# FPGA_part2.net
KiCad netlist of a schematic drawn in Altium Designer
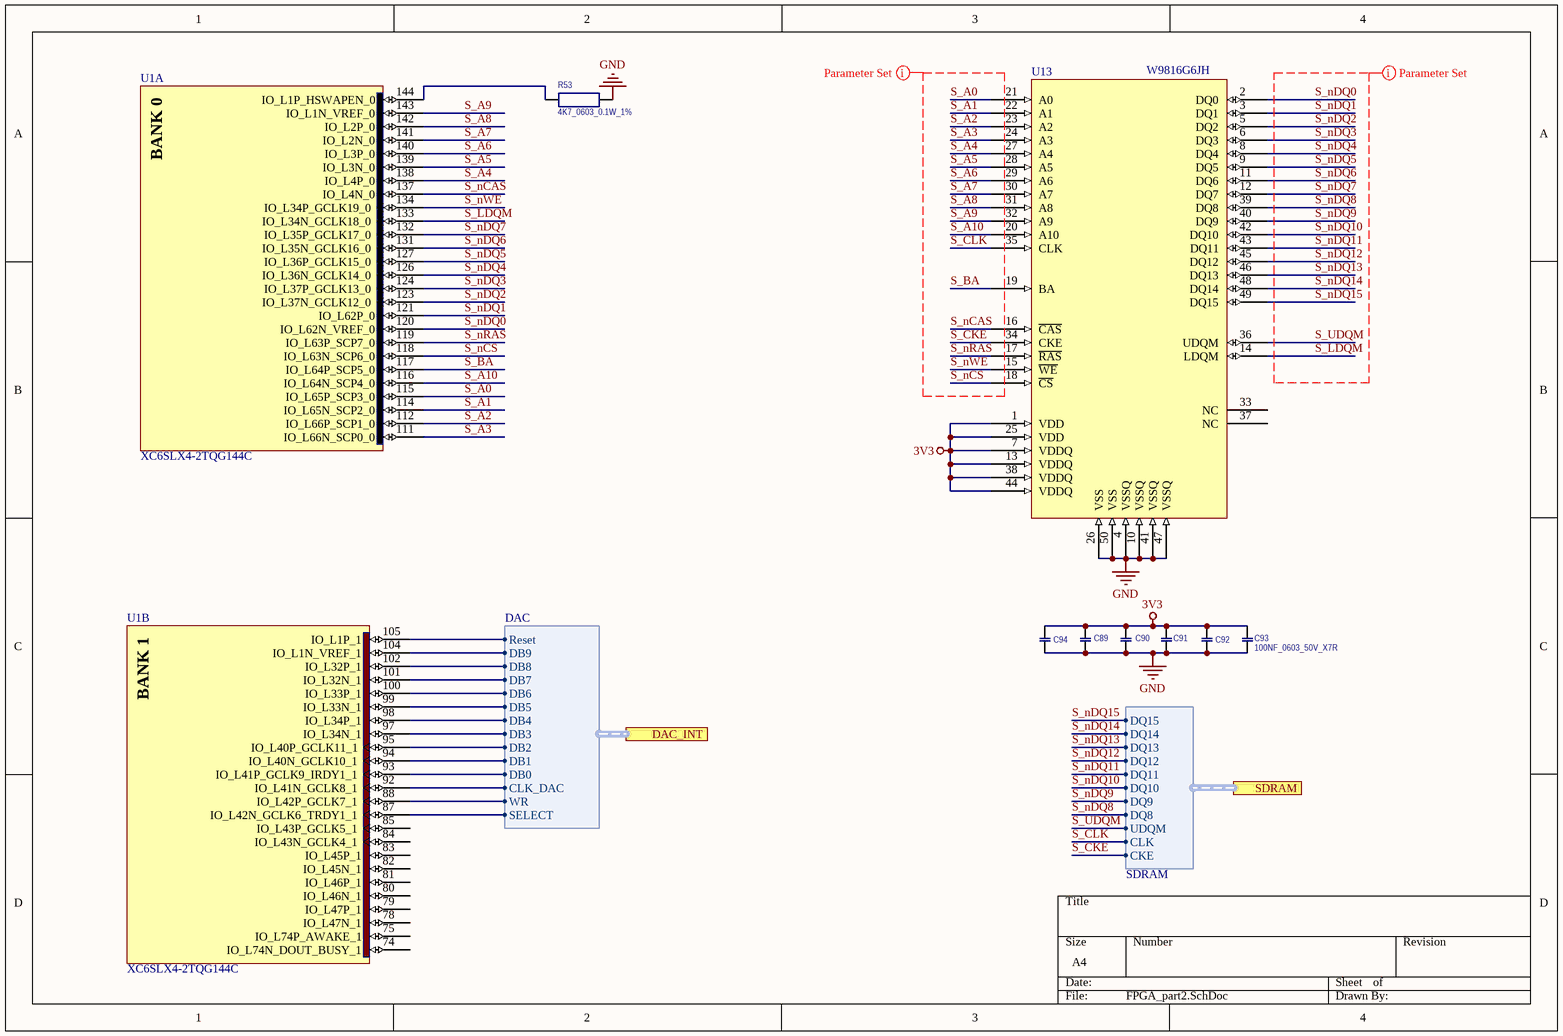
[diagram p0: FPGA_part2.SchDoc]

(export (version "E")
  (design (tool "Eeschema 10.0.6"))
  (components
    (comp (ref "C89")
      (value "100NF_0603_50V_X7R")
      (footprint "CAP0603")
      (description "128-8255    Capacitor MLC-X7R_0603_100NF_10%_50V; C0603C104K5RAC; KEMET; RoHS=Yes")
      (libsource (lib "ONEMULA_V2") (part "100NF_0603_50V_X7R"))
    )
    (comp (ref "C90")
      (value "100NF_0603_50V_X7R")
      (footprint "CAP0603")
      (description "128-8255    Capacitor MLC-X7R_0603_100NF_10%_50V; C0603C104K5RAC; KEMET; RoHS=Yes")
      (libsource (lib "ONEMULA_V2") (part "100NF_0603_50V_X7R"))
    )
    (comp (ref "C91")
      (value "100NF_0603_50V_X7R")
      (footprint "CAP0603")
      (description "128-8255    Capacitor MLC-X7R_0603_100NF_10%_50V; C0603C104K5RAC; KEMET; RoHS=Yes")
      (libsource (lib "ONEMULA_V2") (part "100NF_0603_50V_X7R"))
    )
    (comp (ref "C92")
      (value "100NF_0603_50V_X7R")
      (footprint "CAP0603")
      (description "128-8255    Capacitor MLC-X7R_0603_100NF_10%_50V; C0603C104K5RAC; KEMET; RoHS=Yes")
      (libsource (lib "ONEMULA_V2") (part "100NF_0603_50V_X7R"))
    )
    (comp (ref "C93")
      (value "100NF_0603_50V_X7R")
      (footprint "CAP0603")
      (description "128-8255    Capacitor MLC-X7R_0603_100NF_10%_50V; C0603C104K5RAC; KEMET; RoHS=Yes")
      (libsource (lib "ONEMULA_V2") (part "100NF_0603_50V_X7R"))
    )
    (comp (ref "C94")
      (value "100NF_0603_50V_X7R")
      (footprint "CAP0603")
      (description "128-8255    Capacitor MLC-X7R_0603_100NF_10%_50V; C0603C104K5RAC; KEMET; RoHS=Yes")
      (libsource (lib "ONEMULA_V2") (part "100NF_0603_50V_X7R"))
    )
    (comp (ref "R53")
      (value "4K7_0603_0.1W_1%")
      (footprint "R0603")
      (description "146-9807    RESISTOR MF_0603_4K7_0.1W_1%_75V; CRCW06034K70FKEA; VISHAY; RoHS=Yes")
      (libsource (lib "ONEMULA_V2") (part "4K7_0603_0.1W_1%"))
    )
    (comp (ref "U1")
      (value "XC6SLX4-2TQG144C")
      (footprint "TQG144_L")
      (fields (field (name "PUBLISHER") "Altium Limited"))
      (libsource (lib "Xilinx Spartan-6") (part "XC6SLX4-2TQG144C"))
    )
    (comp (ref "U13")
      (value "W9816G6JH")
      (footprint "SSOP50")
      (libsource (lib "My_library") (part "W9816G6JH"))
    )
  )
  (nets
    (net (code "3") (name "/CLK_DAC") (class "Default")
      (node (ref "U1") (pin "92") (pinfunction "IO_L41N_GCLK8_1_92") (pintype "bidirectional"))
    )
    (net (code "4") (name "/DB0") (class "Default")
      (node (ref "U1") (pin "93") (pinfunction "IO_L41P_GCLK9_IRDY1_1_93") (pintype "bidirectional"))
    )
    (net (code "5") (name "/DB1") (class "Default")
      (node (ref "U1") (pin "94") (pinfunction "IO_L40N_GCLK10_1_94") (pintype "bidirectional"))
    )
    (net (code "6") (name "/DB2") (class "Default")
      (node (ref "U1") (pin "95") (pinfunction "IO_L40P_GCLK11_1_95") (pintype "bidirectional"))
    )
    (net (code "7") (name "/DB3") (class "Default")
      (node (ref "U1") (pin "97") (pinfunction "IO_L34N_1_97") (pintype "bidirectional"))
    )
    (net (code "8") (name "/DB4") (class "Default")
      (node (ref "U1") (pin "98") (pinfunction "IO_L34P_1_98") (pintype "bidirectional"))
    )
    (net (code "9") (name "/DB5") (class "Default")
      (node (ref "U1") (pin "99") (pinfunction "IO_L33N_1_99") (pintype "bidirectional"))
    )
    (net (code "10") (name "/DB6") (class "Default")
      (node (ref "U1") (pin "100") (pinfunction "IO_L33P_1_100") (pintype "bidirectional"))
    )
    (net (code "11") (name "/DB7") (class "Default")
      (node (ref "U1") (pin "101") (pinfunction "IO_L32N_1_101") (pintype "bidirectional"))
    )
    (net (code "12") (name "/DB8") (class "Default")
      (node (ref "U1") (pin "102") (pinfunction "IO_L32P_1_102") (pintype "bidirectional"))
    )
    (net (code "13") (name "/DB9") (class "Default")
      (node (ref "U1") (pin "104") (pinfunction "IO_L1N_VREF_1_104") (pintype "bidirectional"))
    )
    (net (code "14") (name "/Reset") (class "Default")
      (node (ref "U1") (pin "105") (pinfunction "IO_L1P_1_105") (pintype "bidirectional"))
    )
    (net (code "15") (name "/SELECT") (class "Default")
      (node (ref "U1") (pin "87") (pinfunction "IO_L42N_GCLK6_TRDY1_1_87") (pintype "bidirectional"))
    )
    (net (code "16") (name "/S_A0") (class "Default")
      (node (ref "U1") (pin "115") (pinfunction "IO_L65P_SCP3_0_115") (pintype "bidirectional"))
      (node (ref "U13") (pin "21") (pinfunction "A0_21") (pintype "input"))
    )
    (net (code "17") (name "/S_A1") (class "Default")
      (node (ref "U1") (pin "114") (pinfunction "IO_L65N_SCP2_0_114") (pintype "bidirectional"))
      (node (ref "U13") (pin "22") (pinfunction "A1_22") (pintype "input"))
    )
    (net (code "18") (name "/S_A2") (class "Default")
      (node (ref "U1") (pin "112") (pinfunction "IO_L66P_SCP1_0_112") (pintype "bidirectional"))
      (node (ref "U13") (pin "23") (pinfunction "A2_23") (pintype "input"))
    )
    (net (code "19") (name "/S_A3") (class "Default")
      (node (ref "U1") (pin "111") (pinfunction "IO_L66N_SCP0_0_111") (pintype "bidirectional"))
      (node (ref "U13") (pin "24") (pinfunction "A3_24") (pintype "input"))
    )
    (net (code "20") (name "/S_A4") (class "Default")
      (node (ref "U1") (pin "138") (pinfunction "IO_L4P_0_138") (pintype "bidirectional"))
      (node (ref "U13") (pin "27") (pinfunction "A4_27") (pintype "input"))
    )
    (net (code "21") (name "/S_A5") (class "Default")
      (node (ref "U1") (pin "139") (pinfunction "IO_L3N_0_139") (pintype "bidirectional"))
      (node (ref "U13") (pin "28") (pinfunction "A5_28") (pintype "input"))
    )
    (net (code "22") (name "/S_A6") (class "Default")
      (node (ref "U1") (pin "140") (pinfunction "IO_L3P_0_140") (pintype "bidirectional"))
      (node (ref "U13") (pin "29") (pinfunction "A6_29") (pintype "input"))
    )
    (net (code "23") (name "/S_A7") (class "Default")
      (node (ref "U1") (pin "141") (pinfunction "IO_L2N_0_141") (pintype "bidirectional"))
      (node (ref "U13") (pin "30") (pinfunction "A7_30") (pintype "input"))
    )
    (net (code "24") (name "/S_A8") (class "Default")
      (node (ref "U1") (pin "142") (pinfunction "IO_L2P_0_142") (pintype "bidirectional"))
      (node (ref "U13") (pin "31") (pinfunction "A8_31") (pintype "input"))
    )
    (net (code "25") (name "/S_A9") (class "Default")
      (node (ref "U1") (pin "143") (pinfunction "IO_L1N_VREF_0_143") (pintype "bidirectional"))
      (node (ref "U13") (pin "32") (pinfunction "A9_32") (pintype "input"))
    )
    (net (code "26") (name "/S_A10") (class "Default")
      (node (ref "U1") (pin "116") (pinfunction "IO_L64N_SCP4_0_116") (pintype "bidirectional"))
      (node (ref "U13") (pin "20") (pinfunction "A10_20") (pintype "input"))
    )
    (net (code "27") (name "/S_BA") (class "Default")
      (node (ref "U1") (pin "117") (pinfunction "IO_L64P_SCP5_0_117") (pintype "bidirectional"))
      (node (ref "U13") (pin "19") (pinfunction "BA_19") (pintype "input"))
    )
    (net (code "28") (name "/S_CKE") (class "Default")
      (node (ref "U13") (pin "34") (pinfunction "CKE_34") (pintype "input"))
    )
    (net (code "29") (name "/S_CLK") (class "Default")
      (node (ref "U13") (pin "35") (pinfunction "CLK_35") (pintype "input"))
    )
    (net (code "30") (name "/S_LDQM") (class "Default")
      (node (ref "U1") (pin "133") (pinfunction "IO_L34N_GCLK18_0_133") (pintype "bidirectional"))
      (node (ref "U13") (pin "14") (pinfunction "LDQM_14") (pintype "bidirectional"))
    )
    (net (code "31") (name "/S_UDQM") (class "Default")
      (node (ref "U13") (pin "36") (pinfunction "UDQM_36") (pintype "bidirectional"))
    )
    (net (code "32") (name "/S_nCAS") (class "Default")
      (node (ref "U1") (pin "137") (pinfunction "IO_L4N_0_137") (pintype "bidirectional"))
      (node (ref "U13") (pin "16") (pinfunction "~{CAS}_16") (pintype "input"))
    )
    (net (code "33") (name "/S_nCS") (class "Default")
      (node (ref "U1") (pin "118") (pinfunction "IO_L63N_SCP6_0_118") (pintype "bidirectional"))
      (node (ref "U13") (pin "18") (pinfunction "~{CS}_18") (pintype "input"))
    )
    (net (code "34") (name "/S_nDQ0") (class "Default")
      (node (ref "U1") (pin "120") (pinfunction "IO_L62N_VREF_0_120") (pintype "bidirectional"))
      (node (ref "U13") (pin "2") (pinfunction "DQ0_2") (pintype "bidirectional"))
    )
    (net (code "35") (name "/S_nDQ1") (class "Default")
      (node (ref "U1") (pin "121") (pinfunction "IO_L62P_0_121") (pintype "bidirectional"))
      (node (ref "U13") (pin "3") (pinfunction "DQ1_3") (pintype "bidirectional"))
    )
    (net (code "36") (name "/S_nDQ2") (class "Default")
      (node (ref "U1") (pin "123") (pinfunction "IO_L37N_GCLK12_0_123") (pintype "bidirectional"))
      (node (ref "U13") (pin "5") (pinfunction "DQ2_5") (pintype "bidirectional"))
    )
    (net (code "37") (name "/S_nDQ3") (class "Default")
      (node (ref "U1") (pin "124") (pinfunction "IO_L37P_GCLK13_0_124") (pintype "bidirectional"))
      (node (ref "U13") (pin "6") (pinfunction "DQ3_6") (pintype "bidirectional"))
    )
    (net (code "38") (name "/S_nDQ4") (class "Default")
      (node (ref "U1") (pin "126") (pinfunction "IO_L36N_GCLK14_0_126") (pintype "bidirectional"))
      (node (ref "U13") (pin "8") (pinfunction "DQ4_8") (pintype "bidirectional"))
    )
    (net (code "39") (name "/S_nDQ5") (class "Default")
      (node (ref "U1") (pin "127") (pinfunction "IO_L36P_GCLK15_0_127") (pintype "bidirectional"))
      (node (ref "U13") (pin "9") (pinfunction "DQ5_9") (pintype "bidirectional"))
    )
    (net (code "40") (name "/S_nDQ6") (class "Default")
      (node (ref "U1") (pin "131") (pinfunction "IO_L35N_GCLK16_0_131") (pintype "bidirectional"))
      (node (ref "U13") (pin "11") (pinfunction "DQ6_11") (pintype "bidirectional"))
    )
    (net (code "41") (name "/S_nDQ7") (class "Default")
      (node (ref "U1") (pin "132") (pinfunction "IO_L35P_GCLK17_0_132") (pintype "bidirectional"))
      (node (ref "U13") (pin "12") (pinfunction "DQ7_12") (pintype "bidirectional"))
    )
    (net (code "42") (name "/S_nDQ8") (class "Default")
      (node (ref "U13") (pin "39") (pinfunction "DQ8_39") (pintype "bidirectional"))
    )
    (net (code "43") (name "/S_nDQ9") (class "Default")
      (node (ref "U13") (pin "40") (pinfunction "DQ9_40") (pintype "bidirectional"))
    )
    (net (code "44") (name "/S_nDQ10") (class "Default")
      (node (ref "U13") (pin "42") (pinfunction "DQ10_42") (pintype "bidirectional"))
    )
    (net (code "45") (name "/S_nDQ11") (class "Default")
      (node (ref "U13") (pin "43") (pinfunction "DQ11_43") (pintype "bidirectional"))
    )
    (net (code "46") (name "/S_nDQ12") (class "Default")
      (node (ref "U13") (pin "45") (pinfunction "DQ12_45") (pintype "bidirectional"))
    )
    (net (code "47") (name "/S_nDQ13") (class "Default")
      (node (ref "U13") (pin "46") (pinfunction "DQ13_46") (pintype "bidirectional"))
    )
    (net (code "48") (name "/S_nDQ14") (class "Default")
      (node (ref "U13") (pin "48") (pinfunction "DQ14_48") (pintype "bidirectional"))
    )
    (net (code "49") (name "/S_nDQ15") (class "Default")
      (node (ref "U13") (pin "49") (pinfunction "DQ15_49") (pintype "bidirectional"))
    )
    (net (code "50") (name "/S_nRAS") (class "Default")
      (node (ref "U1") (pin "119") (pinfunction "IO_L63P_SCP7_0_119") (pintype "bidirectional"))
      (node (ref "U13") (pin "17") (pinfunction "~{RAS}_17") (pintype "input"))
    )
    (net (code "51") (name "/S_nWE") (class "Default")
      (node (ref "U1") (pin "134") (pinfunction "IO_L34P_GCLK19_0_134") (pintype "bidirectional"))
      (node (ref "U13") (pin "15") (pinfunction "~{WE}_15") (pintype "input"))
    )
    (net (code "52") (name "/WR") (class "Default")
      (node (ref "U1") (pin "88") (pinfunction "IO_L42P_GCLK7_1_88") (pintype "bidirectional"))
    )
    (net (code "55") (name "3V3") (class "Default")
      (node (ref "C89") (pin "1") (pinfunction "1_1") (pintype "passive"))
      (node (ref "C90") (pin "1") (pinfunction "1_1") (pintype "passive"))
      (node (ref "C91") (pin "1") (pinfunction "1_1") (pintype "passive"))
      (node (ref "C92") (pin "1") (pinfunction "1_1") (pintype "passive"))
      (node (ref "C93") (pin "1") (pinfunction "1_1") (pintype "passive"))
      (node (ref "C94") (pin "1") (pinfunction "1_1") (pintype "passive"))
      (node (ref "U13") (pin "1") (pinfunction "VDD_1") (pintype "input"))
      (node (ref "U13") (pin "13") (pinfunction "VDDQ_13") (pintype "input"))
      (node (ref "U13") (pin "25") (pinfunction "VDD_25") (pintype "input"))
      (node (ref "U13") (pin "38") (pinfunction "VDDQ_38") (pintype "input"))
      (node (ref "U13") (pin "44") (pinfunction "VDDQ_44") (pintype "input"))
      (node (ref "U13") (pin "7") (pinfunction "VDDQ_7") (pintype "input"))
    )
    (net (code "56") (name "GND") (class "Default")
      (node (ref "C89") (pin "2") (pinfunction "2_2") (pintype "passive"))
      (node (ref "C90") (pin "2") (pinfunction "2_2") (pintype "passive"))
      (node (ref "C91") (pin "2") (pinfunction "2_2") (pintype "passive"))
      (node (ref "C92") (pin "2") (pinfunction "2_2") (pintype "passive"))
      (node (ref "C93") (pin "2") (pinfunction "2_2") (pintype "passive"))
      (node (ref "C94") (pin "2") (pinfunction "2_2") (pintype "passive"))
      (node (ref "R53") (pin "2") (pinfunction "2_2") (pintype "passive"))
      (node (ref "U13") (pin "10") (pinfunction "VSSQ_10") (pintype "input"))
      (node (ref "U13") (pin "26") (pinfunction "VSS_26") (pintype "input"))
      (node (ref "U13") (pin "4") (pinfunction "VSSQ_4") (pintype "input"))
      (node (ref "U13") (pin "41") (pinfunction "VSSQ_41") (pintype "input"))
      (node (ref "U13") (pin "47") (pinfunction "VSSQ_47") (pintype "input"))
      (node (ref "U13") (pin "50") (pinfunction "VSS_50") (pintype "input"))
    )
    (net (code "57") (name "Net-(U1A-IO_L1P_HSWAPEN_0)") (class "Default")
      (node (ref "R53") (pin "1") (pinfunction "1_1") (pintype "passive"))
      (node (ref "U1") (pin "144") (pinfunction "IO_L1P_HSWAPEN_0_144") (pintype "bidirectional"))
    )
    (net (code "58") (name "unconnected-(U1B-IO_L43N_GCLK4_1-Pad84)") (class "Default")
      (node (ref "U1") (pin "84") (pinfunction "IO_L43N_GCLK4_1_84") (pintype "bidirectional"))
    )
    (net (code "59") (name "unconnected-(U1B-IO_L43P_GCLK5_1-Pad85)") (class "Default")
      (node (ref "U1") (pin "85") (pinfunction "IO_L43P_GCLK5_1_85") (pintype "bidirectional"))
    )
    (net (code "60") (name "unconnected-(U1B-IO_L45N_1-Pad82)") (class "Default")
      (node (ref "U1") (pin "82") (pinfunction "IO_L45N_1_82") (pintype "bidirectional"))
    )
    (net (code "61") (name "unconnected-(U1B-IO_L45P_1-Pad83)") (class "Default")
      (node (ref "U1") (pin "83") (pinfunction "IO_L45P_1_83") (pintype "bidirectional"))
    )
    (net (code "62") (name "unconnected-(U1B-IO_L46N_1-Pad80)") (class "Default")
      (node (ref "U1") (pin "80") (pinfunction "IO_L46N_1_80") (pintype "bidirectional"))
    )
    (net (code "63") (name "unconnected-(U1B-IO_L46P_1-Pad81)") (class "Default")
      (node (ref "U1") (pin "81") (pinfunction "IO_L46P_1_81") (pintype "bidirectional"))
    )
    (net (code "64") (name "unconnected-(U1B-IO_L47N_1-Pad78)") (class "Default")
      (node (ref "U1") (pin "78") (pinfunction "IO_L47N_1_78") (pintype "bidirectional"))
    )
    (net (code "65") (name "unconnected-(U1B-IO_L47P_1-Pad79)") (class "Default")
      (node (ref "U1") (pin "79") (pinfunction "IO_L47P_1_79") (pintype "bidirectional"))
    )
    (net (code "66") (name "unconnected-(U1B-IO_L74N_DOUT_BUSY_1-Pad74)") (class "Default")
      (node (ref "U1") (pin "74") (pinfunction "IO_L74N_DOUT_BUSY_1_74") (pintype "bidirectional"))
    )
    (net (code "67") (name "unconnected-(U1B-IO_L74P_AWAKE_1-Pad75)") (class "Default")
      (node (ref "U1") (pin "75") (pinfunction "IO_L74P_AWAKE_1_75") (pintype "bidirectional"))
    )
    (net (code "68") (name "unconnected-(U13-NC-Pad33)") (class "Default")
      (node (ref "U13") (pin "33") (pinfunction "NC_33") (pintype "passive"))
    )
    (net (code "69") (name "unconnected-(U13-NC-Pad37)") (class "Default")
      (node (ref "U13") (pin "37") (pinfunction "NC_37") (pintype "passive"))
    )
  )
)
